# MCU.net
KiCad netlist of a schematic drawn in Altium Designer
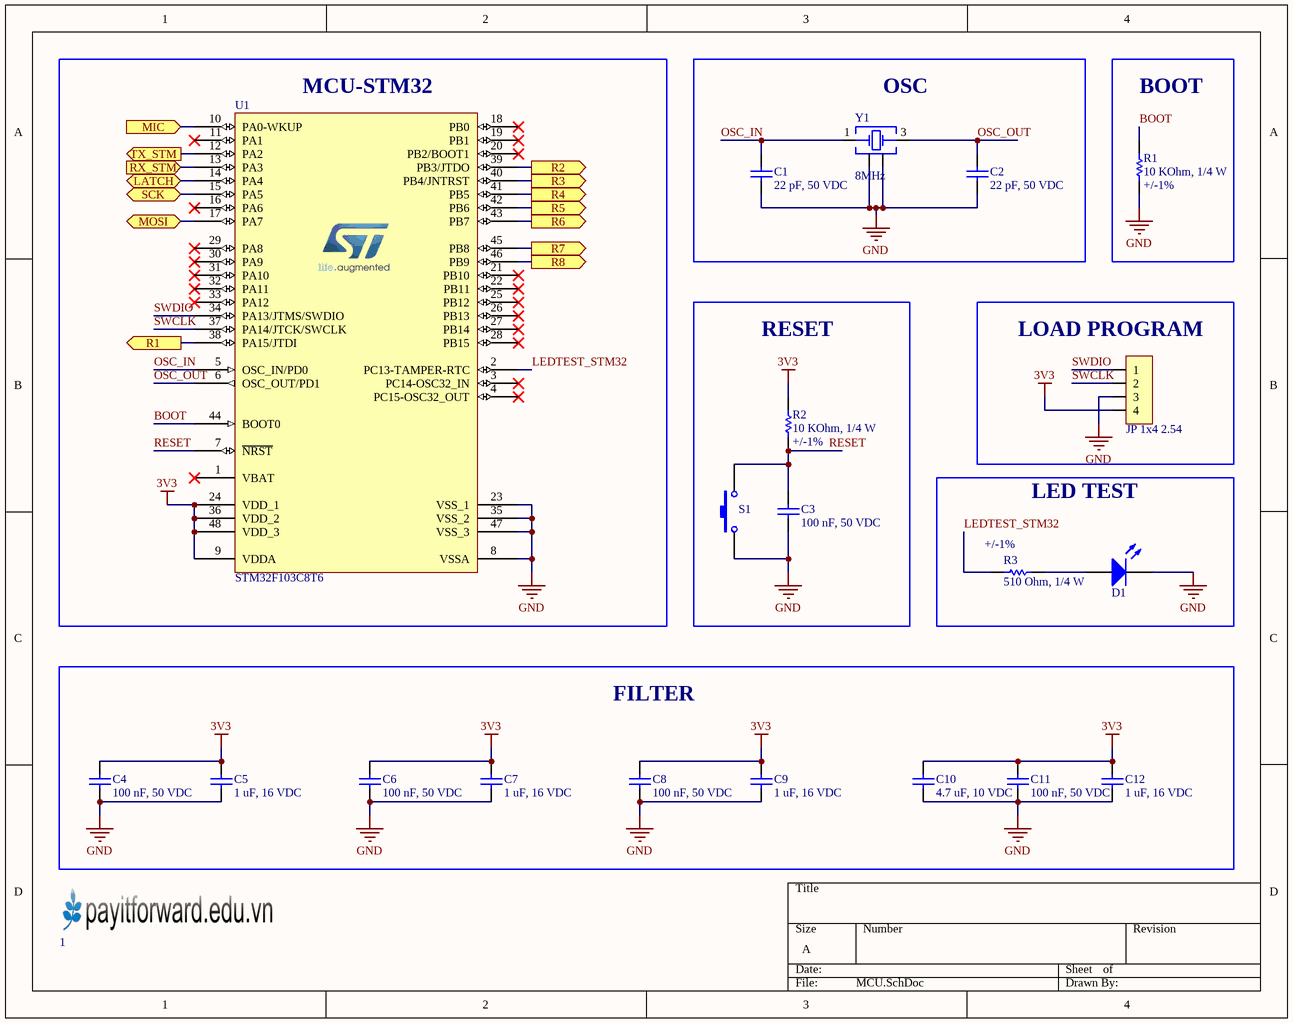
[diagram p0: MCU.SchDoc]

(export (version "E")
  (design (tool "Eeschema 10.0.6"))
  (components
    (comp (ref "1")
      (value "LOGO PIF")
      (footprint "PIF LOGO SMALL TOP")
      (libsource (lib "PIF_Library") (part "LOGO PIF"))
    )
    (comp (ref "C1")
      (value "22 pF, 50 VDC")
      (footprint "CAP_0603")
      (description "CAP, size 0603, 22 pF, 50 VDC")
      (fields (field (name "TOLERANCE") "+/-5%"))
      (libsource (lib "Altium_Ceramic_Cap") (part "0106032200550"))
    )
    (comp (ref "C2")
      (value "22 pF, 50 VDC")
      (footprint "CAP_0603")
      (description "CAP, size 0603, 22 pF, 50 VDC")
      (fields (field (name "TOLERANCE") "+/-5%"))
      (libsource (lib "Altium_Ceramic_Cap") (part "0106032200550"))
    )
    (comp (ref "C3")
      (value "100 nF, 50 VDC")
      (footprint "CAP_0603")
      (description "CAP, size 0603, 100 nF, 50 VDC")
      (fields (field (name "TOLERANCE") "+/-10%"))
      (libsource (lib "Altium_Ceramic_Cap") (part "0106031041050"))
    )
    (comp (ref "C4")
      (value "100 nF, 50 VDC")
      (footprint "CAP_0603")
      (description "CAP, size 0603, 100 nF, 50 VDC")
      (fields (field (name "TOLERANCE") "+/-10%"))
      (libsource (lib "Altium_Ceramic_Cap") (part "0106031041050"))
    )
    (comp (ref "C5")
      (value "1 uF, 16 VDC")
      (footprint "CAP_0603")
      (description "CAP, size 0603, 1 uF, 16 VDC")
      (fields (field (name "TOLERANCE") "+/-10%"))
      (libsource (lib "Altium_Ceramic_Cap") (part "0106031051016"))
    )
    (comp (ref "C6")
      (value "100 nF, 50 VDC")
      (footprint "CAP_0603")
      (description "CAP, size 0603, 100 nF, 50 VDC")
      (fields (field (name "TOLERANCE") "+/-10%"))
      (libsource (lib "Altium_Ceramic_Cap") (part "0106031041050"))
    )
    (comp (ref "C7")
      (value "1 uF, 16 VDC")
      (footprint "CAP_0603")
      (description "CAP, size 0603, 1 uF, 16 VDC")
      (fields (field (name "TOLERANCE") "+/-10%"))
      (libsource (lib "Altium_Ceramic_Cap") (part "0106031051016"))
    )
    (comp (ref "C8")
      (value "100 nF, 50 VDC")
      (footprint "CAP_0603")
      (description "CAP, size 0603, 100 nF, 50 VDC")
      (fields (field (name "TOLERANCE") "+/-10%"))
      (libsource (lib "Altium_Ceramic_Cap") (part "0106031041050"))
    )
    (comp (ref "C9")
      (value "1 uF, 16 VDC")
      (footprint "CAP_0603")
      (description "CAP, size 0603, 1 uF, 16 VDC")
      (fields (field (name "TOLERANCE") "+/-10%"))
      (libsource (lib "Altium_Ceramic_Cap") (part "0106031051016"))
    )
    (comp (ref "C10")
      (value "4.7 uF, 10 VDC")
      (footprint "CAP_0603")
      (description "CAP, size 0603, 4.7 uF, 10 VDC")
      (fields (field (name "TOLERANCE") "+/-10%"))
      (libsource (lib "Altium_Ceramic_Cap") (part "0106034751010"))
    )
    (comp (ref "C11")
      (value "100 nF, 50 VDC")
      (footprint "CAP_0603")
      (description "CAP, size 0603, 100 nF, 50 VDC")
      (fields (field (name "TOLERANCE") "+/-10%"))
      (libsource (lib "Altium_Ceramic_Cap") (part "0106031041050"))
    )
    (comp (ref "C12")
      (value "1 uF, 16 VDC")
      (footprint "CAP_0603")
      (description "CAP, size 0603, 1 uF, 16 VDC")
      (fields (field (name "TOLERANCE") "+/-10%"))
      (libsource (lib "Altium_Ceramic_Cap") (part "0106031051016"))
    )
    (comp (ref "D1")
      (value "LED SMD")
      (footprint "LED_0805_Blue")
      (description "LED")
      (libsource (lib "PIF_Library") (part "LED SMD"))
    )
    (comp (ref "JP1")
      (value "JP 1x4 2.54")
      (footprint "JP 1x4 DT")
      (description "Cắm")
      (libsource (lib "Jump") (part "JP 1x4 2.54 Duc Thang"))
    )
    (comp (ref "R1")
      (value "10 KOhm, 1/4 W")
      (footprint "resistor_0603")
      (description "RES, size 0603, 10 KOhm, 1/4 W")
      (fields (field (name "RESISTANCE TOLERANCE") "+/-1%"))
      (libsource (lib "Altium_Resistor") (part "0006031031"))
    )
    (comp (ref "R2")
      (value "10 KOhm, 1/4 W")
      (footprint "resistor_0603")
      (description "RES, size 0603, 10 KOhm, 1/4 W")
      (fields (field (name "RESISTANCE TOLERANCE") "+/-1%"))
      (libsource (lib "Altium_Resistor") (part "0006031031"))
    )
    (comp (ref "R3")
      (value "510 Ohm, 1/4 W")
      (footprint "resistor_0603")
      (description "RES, size 0603, 510 Ohm, 1/4 W")
      (fields (field (name "RESISTANCE TOLERANCE") "+/-1%"))
      (libsource (lib "Altium_Resistor") (part "0006035111"))
    )
    (comp (ref "S1")
      (value "Tact SW - 2Pin")
      (footprint "SW-SMD")
      (description "Switch button 2 pin")
      (libsource (lib "PIF_Library") (part "Tact SW - 2Pin"))
    )
    (comp (ref "U1")
      (value "STM32F103C8T6")
      (footprint "STM32F103C8T6")
      (description "ARM Microcontrollers - MCU 32BIT Cortex M3 64KB 20KB RAM 2X12 ADC")
      (fields (field (name "MANUFACTURER") "STM"))
      (libsource (lib "Altium_MCU") (part "STM32F103C8T6"))
    )
    (comp (ref "Y1")
      (value "8MHz")
      (footprint "WE-XTAL_CFPX-180")
      (description "WE-XTAL Quartz Crystal, SMT, CFPX-180, 8MHz, +/-30ppm")
      (fields
        (field (name "MANUFACTURER PART NUMBER") "830108313809")
        (field (name "MANUFACTURER") "Wurth Elektronik")
      )
      (libsource (lib "Altium_WE-XTAL (rev20c)") (part "830108313809"))
    )
  )
  (nets
    (net (code "1") (name "/BOOT") (class "Default")
      (node (ref "R1") (pin "2") (pinfunction "2_2") (pintype "passive"))
      (node (ref "U1") (pin "44") (pinfunction "BOOT0_44") (pintype "input"))
    )
    (net (code "2") (name "/LATCH") (class "Default")
      (node (ref "U1") (pin "14") (pinfunction "PA4_14") (pintype "bidirectional"))
    )
    (net (code "3") (name "/LEDTEST_STM32") (class "Default")
      (node (ref "R3") (pin "1") (pinfunction "1_1") (pintype "passive"))
      (node (ref "U1") (pin "2") (pinfunction "PC13-TAMPER-RTC_2") (pintype "bidirectional"))
    )
    (net (code "4") (name "/MIC") (class "Default")
      (node (ref "U1") (pin "10") (pinfunction "PA0-WKUP_10") (pintype "bidirectional"))
    )
    (net (code "5") (name "/MOSI") (class "Default")
      (node (ref "U1") (pin "17") (pinfunction "PA7_17") (pintype "bidirectional"))
    )
    (net (code "6") (name "/OSC_IN") (class "Default")
      (node (ref "C1") (pin "2") (pinfunction "2_2") (pintype "passive"))
      (node (ref "U1") (pin "5") (pinfunction "OSC_IN/PD0_5") (pintype "input"))
      (node (ref "Y1") (pin "1") (pinfunction "Crystal_1") (pintype "passive"))
    )
    (net (code "7") (name "/OSC_OUT") (class "Default")
      (node (ref "C2") (pin "2") (pinfunction "2_2") (pintype "passive"))
      (node (ref "U1") (pin "6") (pinfunction "OSC_OUT/PD1_6") (pintype "output"))
      (node (ref "Y1") (pin "3") (pinfunction "Crystal_3") (pintype "passive"))
    )
    (net (code "8") (name "/R1") (class "Default")
      (node (ref "U1") (pin "38") (pinfunction "PA15/JTDI_38") (pintype "bidirectional"))
    )
    (net (code "9") (name "/R2") (class "Default")
      (node (ref "U1") (pin "39") (pinfunction "PB3/JTDO_39") (pintype "bidirectional"))
    )
    (net (code "10") (name "/R3") (class "Default")
      (node (ref "U1") (pin "40") (pinfunction "PB4/JNTRST_40") (pintype "bidirectional"))
    )
    (net (code "11") (name "/R4") (class "Default")
      (node (ref "U1") (pin "41") (pinfunction "PB5_41") (pintype "bidirectional"))
    )
    (net (code "12") (name "/R5") (class "Default")
      (node (ref "U1") (pin "42") (pinfunction "PB6_42") (pintype "bidirectional"))
    )
    (net (code "13") (name "/R6") (class "Default")
      (node (ref "U1") (pin "43") (pinfunction "PB7_43") (pintype "bidirectional"))
    )
    (net (code "14") (name "/R7") (class "Default")
      (node (ref "U1") (pin "45") (pinfunction "PB8_45") (pintype "bidirectional"))
    )
    (net (code "15") (name "/R8") (class "Default")
      (node (ref "U1") (pin "46") (pinfunction "PB9_46") (pintype "bidirectional"))
    )
    (net (code "16") (name "/RESET") (class "Default")
      (node (ref "C3") (pin "2") (pinfunction "2_2") (pintype "passive"))
      (node (ref "R2") (pin "1") (pinfunction "1_1") (pintype "passive"))
      (node (ref "S1") (pin "2") (pinfunction "2_2") (pintype "passive"))
      (node (ref "U1") (pin "7") (pinfunction "~{NRST}_7") (pintype "bidirectional"))
    )
    (net (code "17") (name "/RX_STM") (class "Default")
      (node (ref "U1") (pin "13") (pinfunction "PA3_13") (pintype "bidirectional"))
    )
    (net (code "18") (name "/SCK") (class "Default")
      (node (ref "U1") (pin "15") (pinfunction "PA5_15") (pintype "bidirectional"))
    )
    (net (code "19") (name "/SWCLK") (class "Default")
      (node (ref "JP1") (pin "2") (pinfunction "2_2") (pintype "passive"))
      (node (ref "U1") (pin "37") (pinfunction "PA14/JTCK/SWCLK_37") (pintype "bidirectional"))
    )
    (net (code "20") (name "/SWDIO") (class "Default")
      (node (ref "JP1") (pin "1") (pinfunction "1_1") (pintype "passive"))
      (node (ref "U1") (pin "34") (pinfunction "PA13/JTMS/SWDIO_34") (pintype "bidirectional"))
    )
    (net (code "21") (name "/TX_STM") (class "Default")
      (node (ref "U1") (pin "12") (pinfunction "PA2_12") (pintype "bidirectional"))
    )
    (net (code "22") (name "3V3") (class "Default")
      (node (ref "C10") (pin "2") (pinfunction "2_2") (pintype "passive"))
      (node (ref "C11") (pin "2") (pinfunction "2_2") (pintype "passive"))
      (node (ref "C12") (pin "2") (pinfunction "2_2") (pintype "passive"))
      (node (ref "C4") (pin "2") (pinfunction "2_2") (pintype "passive"))
      (node (ref "C5") (pin "2") (pinfunction "2_2") (pintype "passive"))
      (node (ref "C6") (pin "2") (pinfunction "2_2") (pintype "passive"))
      (node (ref "C7") (pin "2") (pinfunction "2_2") (pintype "passive"))
      (node (ref "C8") (pin "2") (pinfunction "2_2") (pintype "passive"))
      (node (ref "C9") (pin "2") (pinfunction "2_2") (pintype "passive"))
      (node (ref "JP1") (pin "4") (pinfunction "4_4") (pintype "passive"))
      (node (ref "R2") (pin "2") (pinfunction "2_2") (pintype "passive"))
      (node (ref "U1") (pin "24") (pinfunction "VDD_1_24") (pintype "power_in"))
      (node (ref "U1") (pin "36") (pinfunction "VDD_2_36") (pintype "power_in"))
      (node (ref "U1") (pin "48") (pinfunction "VDD_3_48") (pintype "power_in"))
      (node (ref "U1") (pin "9") (pinfunction "VDDA_9") (pintype "power_in"))
    )
    (net (code "23") (name "GND") (class "Default")
      (node (ref "C1") (pin "1") (pinfunction "1_1") (pintype "passive"))
      (node (ref "C10") (pin "1") (pinfunction "1_1") (pintype "passive"))
      (node (ref "C11") (pin "1") (pinfunction "1_1") (pintype "passive"))
      (node (ref "C12") (pin "1") (pinfunction "1_1") (pintype "passive"))
      (node (ref "C2") (pin "1") (pinfunction "1_1") (pintype "passive"))
      (node (ref "C3") (pin "1") (pinfunction "1_1") (pintype "passive"))
      (node (ref "C4") (pin "1") (pinfunction "1_1") (pintype "passive"))
      (node (ref "C5") (pin "1") (pinfunction "1_1") (pintype "passive"))
      (node (ref "C6") (pin "1") (pinfunction "1_1") (pintype "passive"))
      (node (ref "C7") (pin "1") (pinfunction "1_1") (pintype "passive"))
      (node (ref "C8") (pin "1") (pinfunction "1_1") (pintype "passive"))
      (node (ref "C9") (pin "1") (pinfunction "1_1") (pintype "passive"))
      (node (ref "D1") (pin "2") (pinfunction "K_2") (pintype "passive"))
      (node (ref "JP1") (pin "3") (pinfunction "3_3") (pintype "passive"))
      (node (ref "R1") (pin "1") (pinfunction "1_1") (pintype "passive"))
      (node (ref "S1") (pin "1") (pinfunction "1_1") (pintype "passive"))
      (node (ref "U1") (pin "23") (pinfunction "VSS_1_23") (pintype "power_in"))
      (node (ref "U1") (pin "35") (pinfunction "VSS_2_35") (pintype "power_in"))
      (node (ref "U1") (pin "47") (pinfunction "VSS_3_47") (pintype "power_in"))
      (node (ref "U1") (pin "8") (pinfunction "VSSA_8") (pintype "power_in"))
      (node (ref "Y1") (pin "2") (pinfunction "GND&Lid_2") (pintype "passive"))
      (node (ref "Y1") (pin "4") (pinfunction "GND&Lid_4") (pintype "passive"))
    )
    (net (code "24") (name "Net-(D1-A)") (class "Default")
      (node (ref "D1") (pin "1") (pinfunction "A_1") (pintype "passive"))
      (node (ref "R3") (pin "2") (pinfunction "2_2") (pintype "passive"))
    )
    (net (code "25") (name "unconnected-(U1-PA1-Pad11)") (class "Default")
      (node (ref "U1") (pin "11") (pinfunction "PA1_11") (pintype "bidirectional+no_connect"))
    )
    (net (code "26") (name "unconnected-(U1-PA6-Pad16)") (class "Default")
      (node (ref "U1") (pin "16") (pinfunction "PA6_16") (pintype "bidirectional+no_connect"))
    )
    (net (code "27") (name "unconnected-(U1-PA8-Pad29)") (class "Default")
      (node (ref "U1") (pin "29") (pinfunction "PA8_29") (pintype "bidirectional+no_connect"))
    )
    (net (code "28") (name "unconnected-(U1-PA9-Pad30)") (class "Default")
      (node (ref "U1") (pin "30") (pinfunction "PA9_30") (pintype "bidirectional+no_connect"))
    )
    (net (code "29") (name "unconnected-(U1-PA10-Pad31)") (class "Default")
      (node (ref "U1") (pin "31") (pinfunction "PA10_31") (pintype "bidirectional+no_connect"))
    )
    (net (code "30") (name "unconnected-(U1-PA11-Pad32)") (class "Default")
      (node (ref "U1") (pin "32") (pinfunction "PA11_32") (pintype "bidirectional+no_connect"))
    )
    (net (code "31") (name "unconnected-(U1-PA12-Pad33)") (class "Default")
      (node (ref "U1") (pin "33") (pinfunction "PA12_33") (pintype "bidirectional+no_connect"))
    )
    (net (code "32") (name "unconnected-(U1-PB0-Pad18)") (class "Default")
      (node (ref "U1") (pin "18") (pinfunction "PB0_18") (pintype "bidirectional+no_connect"))
    )
    (net (code "33") (name "unconnected-(U1-PB1-Pad19)") (class "Default")
      (node (ref "U1") (pin "19") (pinfunction "PB1_19") (pintype "bidirectional+no_connect"))
    )
    (net (code "34") (name "unconnected-(U1-PB2{slash}BOOT1-Pad20)") (class "Default")
      (node (ref "U1") (pin "20") (pinfunction "PB2/BOOT1_20") (pintype "bidirectional+no_connect"))
    )
    (net (code "35") (name "unconnected-(U1-PB10-Pad21)") (class "Default")
      (node (ref "U1") (pin "21") (pinfunction "PB10_21") (pintype "bidirectional+no_connect"))
    )
    (net (code "36") (name "unconnected-(U1-PB11-Pad22)") (class "Default")
      (node (ref "U1") (pin "22") (pinfunction "PB11_22") (pintype "bidirectional+no_connect"))
    )
    (net (code "37") (name "unconnected-(U1-PB12-Pad25)") (class "Default")
      (node (ref "U1") (pin "25") (pinfunction "PB12_25") (pintype "bidirectional+no_connect"))
    )
    (net (code "38") (name "unconnected-(U1-PB13-Pad26)") (class "Default")
      (node (ref "U1") (pin "26") (pinfunction "PB13_26") (pintype "bidirectional+no_connect"))
    )
    (net (code "39") (name "unconnected-(U1-PB14-Pad27)") (class "Default")
      (node (ref "U1") (pin "27") (pinfunction "PB14_27") (pintype "bidirectional+no_connect"))
    )
    (net (code "40") (name "unconnected-(U1-PB15-Pad28)") (class "Default")
      (node (ref "U1") (pin "28") (pinfunction "PB15_28") (pintype "bidirectional+no_connect"))
    )
    (net (code "41") (name "unconnected-(U1-PC14-OSC32_IN-Pad3)") (class "Default")
      (node (ref "U1") (pin "3") (pinfunction "PC14-OSC32_IN_3") (pintype "bidirectional+no_connect"))
    )
    (net (code "42") (name "unconnected-(U1-PC15-OSC32_OUT-Pad4)") (class "Default")
      (node (ref "U1") (pin "4") (pinfunction "PC15-OSC32_OUT_4") (pintype "bidirectional+no_connect"))
    )
    (net (code "43") (name "unconnected-(U1-VBAT-Pad1)") (class "Default")
      (node (ref "U1") (pin "1") (pinfunction "VBAT_1") (pintype "power_in+no_connect"))
    )
  )
)
